# Xbee_Remote_v1_0.net
KiCad netlist of a schematic drawn in EAGLE
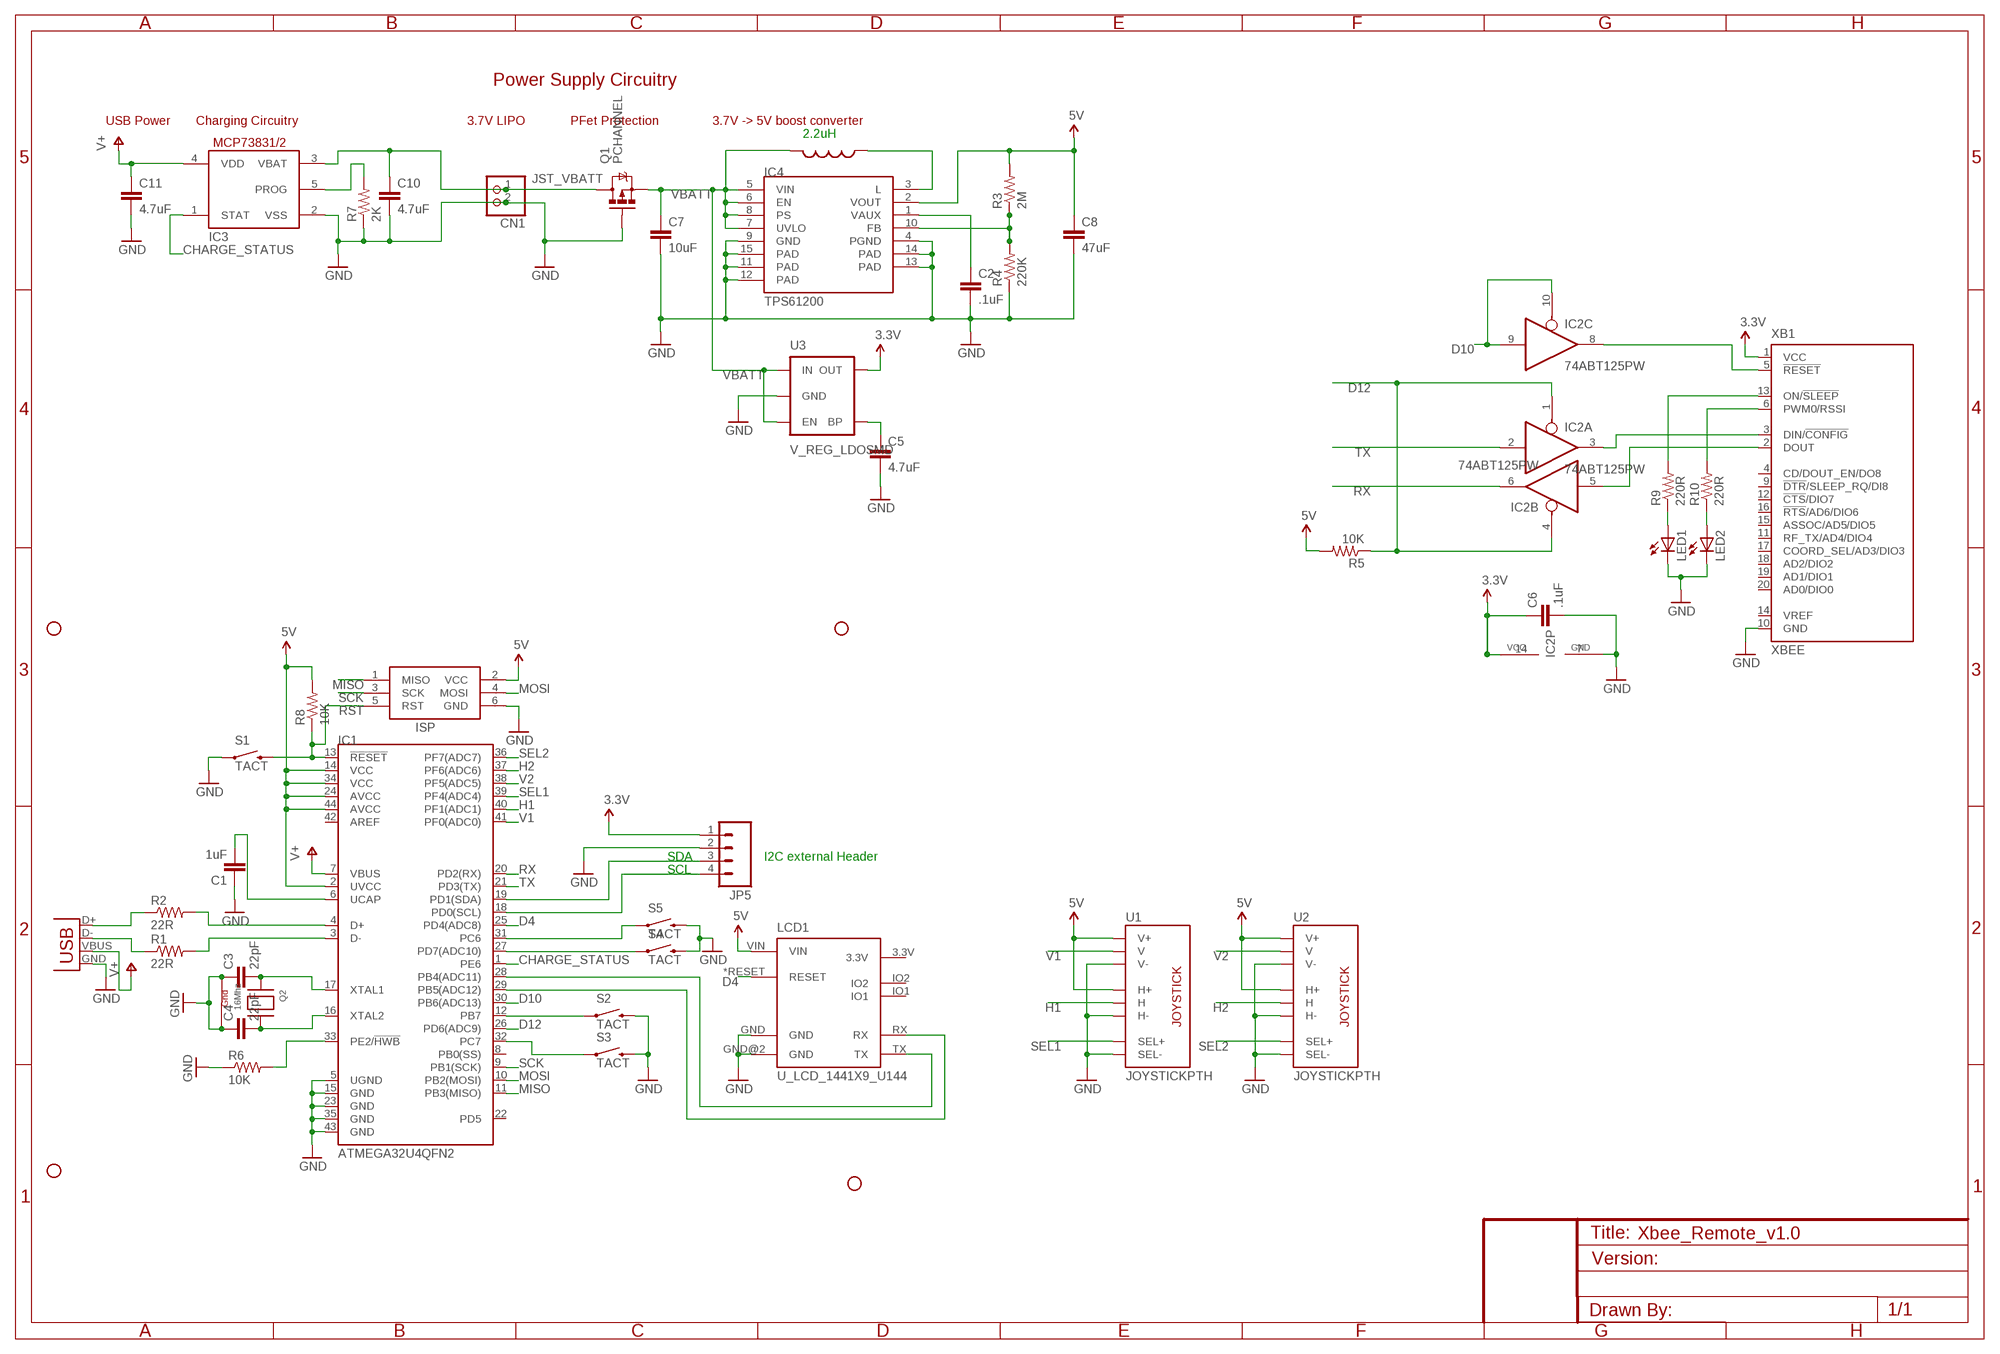
[diagram p0: schematic, sheet 1]

(export (version "E")
  (design (tool "Eeschema 10.0.6"))
  (components
    (comp (ref "C1")
      (value "1uF")
      (footprint "eagle-import:0805")
      (libsource (lib "eagle-import") (part "CAP0805"))
    )
    (comp (ref "C2")
      (value ".1uF")
      (footprint "eagle-import:0805")
      (libsource (lib "eagle-import") (part "CAP0805"))
    )
    (comp (ref "C3")
      (value "22pF")
      (footprint "eagle-import:0805")
      (libsource (lib "eagle-import") (part "CAP0805"))
    )
    (comp (ref "C4")
      (value "22pF")
      (footprint "eagle-import:0805")
      (libsource (lib "eagle-import") (part "CAP0805"))
    )
    (comp (ref "C5")
      (value "4.7uF")
      (footprint "eagle-import:0805")
      (libsource (lib "eagle-import") (part "CAP0805"))
    )
    (comp (ref "C6")
      (value ".1uF")
      (footprint "eagle-import:0805")
      (libsource (lib "eagle-import") (part "CAP0805"))
    )
    (comp (ref "C7")
      (value "10uF")
      (footprint "eagle-import:0805")
      (libsource (lib "eagle-import") (part "CAP0805"))
    )
    (comp (ref "C8")
      (value "47uF")
      (footprint "eagle-import:1206")
      (libsource (lib "eagle-import") (part "CAP1206"))
    )
    (comp (ref "C10")
      (value "4.7uF")
      (footprint "eagle-import:0805")
      (libsource (lib "eagle-import") (part "CAP0805"))
    )
    (comp (ref "C11")
      (value "4.7uF")
      (footprint "eagle-import:0805")
      (libsource (lib "eagle-import") (part "CAP0805"))
    )
    (comp (ref "CN1")
      (value "JST_2PIN-SMT-RA")
      (footprint "eagle-import:JST-PH-2-SMT-RA")
      (libsource (lib "eagle-import") (part "JST_2PIN-SMT-RA"))
    )
    (comp (ref "IC1")
      (value "ATMEGA32U4QFN2")
      (footprint "eagle-import:QFN-44-NOPAD")
      (libsource (lib "eagle-import") (part "ATMEGA32U4QFN2"))
    )
    (comp (ref "IC2")
      (value "74ABT125PW")
      (footprint "eagle-import:TSSOP14")
      (libsource (lib "eagle-import") (part "74125PWABT"))
    )
    (comp (ref "IC3")
      (value "MCP73831/OT")
      (footprint "eagle-import:SOT23-5L")
      (libsource (lib "eagle-import") (part "MCP73831/OT"))
    )
    (comp (ref "IC4")
      (value "TPS61200")
      (footprint "eagle-import:QFN-10_PAD")
      (libsource (lib "eagle-import") (part "TPS61200"))
    )
    (comp (ref "ISP")
      (value "AVRISP-6")
      (footprint "eagle-import:AVRISP")
      (libsource (lib "eagle-import") (part "AVRISP-6"))
    )
    (comp (ref "JP1")
      (value "STAND-OFF")
      (footprint "eagle-import:STAND-OFF")
      (libsource (lib "eagle-import") (part "STAND-OFF"))
    )
    (comp (ref "JP2")
      (value "STAND-OFF")
      (footprint "eagle-import:STAND-OFF")
      (libsource (lib "eagle-import") (part "STAND-OFF"))
    )
    (comp (ref "JP3")
      (value "STAND-OFF")
      (footprint "eagle-import:STAND-OFF")
      (libsource (lib "eagle-import") (part "STAND-OFF"))
    )
    (comp (ref "JP4")
      (value "STAND-OFF")
      (footprint "eagle-import:STAND-OFF")
      (libsource (lib "eagle-import") (part "STAND-OFF"))
    )
    (comp (ref "JP5")
      (value "M04PTH")
      (footprint "eagle-import:1X04")
      (libsource (lib "eagle-import") (part "M04PTH"))
    )
    (comp (ref "L1")
      (value "2.2uH")
      (footprint "eagle-import:COILCRAFT_EPL2014")
      (libsource (lib "eagle-import") (part "INDUCTOREPL2014"))
    )
    (comp (ref "LCD1")
      (value "U_LCD_1441X9_U144")
      (footprint "eagle-import:U_LCD_144")
      (libsource (lib "eagle-import") (part "U_LCD_1441X9_U144"))
    )
    (comp (ref "LED1")
      (value "LEDCHIPLED_0805")
      (footprint "eagle-import:CHIPLED_0805")
      (libsource (lib "eagle-import") (part "LEDCHIPLED_0805"))
    )
    (comp (ref "LED2")
      (value "LEDCHIPLED_0805")
      (footprint "eagle-import:CHIPLED_0805")
      (libsource (lib "eagle-import") (part "LEDCHIPLED_0805"))
    )
    (comp (ref "Q1")
      (value "PCHANNEL")
      (footprint "eagle-import:SOT23-3")
      (libsource (lib "eagle-import") (part "MOSFET-PCHANNELSMD"))
    )
    (comp (ref "Q2")
      (value "16Mhz")
      (footprint "eagle-import:NX3225")
      (libsource (lib "eagle-import") (part "XTAL-4-3225"))
    )
    (comp (ref "R1")
      (value "22R")
      (footprint "eagle-import:0805")
      (libsource (lib "eagle-import") (part "RESISTOR"))
    )
    (comp (ref "R2")
      (value "22R")
      (footprint "eagle-import:0805")
      (libsource (lib "eagle-import") (part "RESISTOR"))
    )
    (comp (ref "R3")
      (value "2M")
      (footprint "eagle-import:0805")
      (libsource (lib "eagle-import") (part "RESISTOR"))
    )
    (comp (ref "R4")
      (value "220K")
      (footprint "eagle-import:0805")
      (libsource (lib "eagle-import") (part "RESISTOR"))
    )
    (comp (ref "R5")
      (value "10K")
      (footprint "eagle-import:0805")
      (libsource (lib "eagle-import") (part "RESISTOR"))
    )
    (comp (ref "R6")
      (value "10K")
      (footprint "eagle-import:0805")
      (libsource (lib "eagle-import") (part "RESISTOR"))
    )
    (comp (ref "R7")
      (value "2K")
      (footprint "eagle-import:0805")
      (libsource (lib "eagle-import") (part "RESISTOR"))
    )
    (comp (ref "R8")
      (value "10K")
      (footprint "eagle-import:0805")
      (libsource (lib "eagle-import") (part "RESISTOR"))
    )
    (comp (ref "R9")
      (value "220R")
      (footprint "eagle-import:0805")
      (libsource (lib "eagle-import") (part "RESISTOR"))
    )
    (comp (ref "R10")
      (value "220R")
      (footprint "eagle-import:0805")
      (libsource (lib "eagle-import") (part "RESISTOR"))
    )
    (comp (ref "S1")
      (value "TACT")
      (footprint "eagle-import:TACTILE_SWITCH_SMD")
      (libsource (lib "eagle-import") (part "SWITCH-MOMENTARY-2SMD"))
    )
    (comp (ref "S2")
      (value "TACT")
      (footprint "eagle-import:TACTILE_SWITCH_SMD")
      (libsource (lib "eagle-import") (part "SWITCH-MOMENTARY-2SMD"))
    )
    (comp (ref "S3")
      (value "TACT")
      (footprint "eagle-import:TACTILE_SWITCH_SMD")
      (libsource (lib "eagle-import") (part "SWITCH-MOMENTARY-2SMD"))
    )
    (comp (ref "S4")
      (value "TACT")
      (footprint "eagle-import:TACTILE_SWITCH_SMD")
      (libsource (lib "eagle-import") (part "SWITCH-MOMENTARY-2SMD"))
    )
    (comp (ref "S5")
      (value "TACT")
      (footprint "eagle-import:TACTILE_SWITCH_SMD")
      (libsource (lib "eagle-import") (part "SWITCH-MOMENTARY-2SMD"))
    )
    (comp (ref "U1")
      (value "JOYSTICKPTH")
      (footprint "eagle-import:JOYSTICK")
      (libsource (lib "eagle-import") (part "JOYSTICKPTH"))
    )
    (comp (ref "U2")
      (value "JOYSTICKPTH")
      (footprint "eagle-import:JOYSTICK")
      (libsource (lib "eagle-import") (part "JOYSTICKPTH"))
    )
    (comp (ref "U3")
      (value "V_REG_LDOSMD")
      (footprint "eagle-import:SOT23-5")
      (libsource (lib "eagle-import") (part "V_REG_LDOSMD"))
    )
    (comp (ref "X1")
      (value "USB-MICROB")
      (footprint "eagle-import:USB-MICROB")
      (libsource (lib "eagle-import") (part "USB-MICROB"))
    )
    (comp (ref "XB1")
      (value "XBEE")
      (footprint "eagle-import:XBEE")
      (fields (field (name "MPN") "XBP24-Z7UIT-004"))
      (libsource (lib "eagle-import") (part "XBEE"))
    )
  )
  (nets
    (net (code "1") (name "/CHARGE_STATUS") (class "Default")
      (node (ref "IC1") (pin "1") (pinfunction "PE6_1") (pintype "bidirectional"))
      (node (ref "IC3") (pin "1") (pinfunction "STAT_1") (pintype "output"))
    )
    (net (code "2") (name "/D4") (class "Default")
      (node (ref "IC1") (pin "25") (pinfunction "PD4(ADC8)_25") (pintype "bidirectional"))
      (node (ref "LCD1") (pin "*RESET") (pinfunction "RESET_*RESET") (pintype "input"))
    )
    (net (code "3") (name "/D10") (class "Default")
      (node (ref "IC1") (pin "30") (pinfunction "PB6(ADC13)_30") (pintype "bidirectional"))
      (node (ref "IC2") (pin "10") (pinfunction "OE_10") (pintype "input"))
      (node (ref "IC2") (pin "9") (pinfunction "I_9") (pintype "input"))
    )
    (net (code "4") (name "/D12") (class "Default")
      (node (ref "IC1") (pin "26") (pinfunction "PD6(ADC9)_26") (pintype "bidirectional"))
      (node (ref "IC2") (pin "1") (pinfunction "OE_1") (pintype "input"))
      (node (ref "IC2") (pin "4") (pinfunction "OE_4") (pintype "input"))
      (node (ref "R5") (pin "1") (pinfunction "1_1") (pintype "passive"))
    )
    (net (code "5") (name "/H1") (class "Default")
      (node (ref "IC1") (pin "40") (pinfunction "PF1(ADC1)_40") (pintype "bidirectional"))
      (node (ref "U1") (pin "H2") (pinfunction "H_H2") (pintype "bidirectional"))
    )
    (net (code "6") (name "/H2") (class "Default")
      (node (ref "IC1") (pin "37") (pinfunction "PF6(ADC6)_37") (pintype "bidirectional"))
      (node (ref "U2") (pin "H2") (pinfunction "H_H2") (pintype "bidirectional"))
    )
    (net (code "7") (name "/JST_VBATT") (class "Default")
      (node (ref "C10") (pin "1") (pinfunction "1_1") (pintype "passive"))
      (node (ref "CN1") (pin "1") (pinfunction "2_1") (pintype "passive"))
      (node (ref "IC3") (pin "3") (pinfunction "VBAT_3") (pintype "bidirectional"))
      (node (ref "Q1") (pin "3") (pinfunction "D_3") (pintype "passive"))
    )
    (net (code "8") (name "/MISO") (class "Default")
      (node (ref "IC1") (pin "11") (pinfunction "PB3(MISO)_11") (pintype "bidirectional"))
      (node (ref "ISP") (pin "1") (pinfunction "MISO_1") (pintype "input"))
    )
    (net (code "9") (name "/MOSI") (class "Default")
      (node (ref "IC1") (pin "10") (pinfunction "PB2(MOSI)_10") (pintype "bidirectional"))
      (node (ref "ISP") (pin "4") (pinfunction "MOSI_4") (pintype "output"))
    )
    (net (code "10") (name "/RST") (class "Default")
      (node (ref "IC1") (pin "13") (pinfunction "~{RESET}_13") (pintype "bidirectional"))
      (node (ref "ISP") (pin "5") (pinfunction "RST_5") (pintype "output"))
      (node (ref "R8") (pin "1") (pinfunction "1_1") (pintype "passive"))
      (node (ref "S1") (pin "3") (pinfunction "2_3") (pintype "passive"))
    )
    (net (code "11") (name "/RX") (class "Default")
      (node (ref "IC1") (pin "20") (pinfunction "PD2(RX)_20") (pintype "bidirectional"))
      (node (ref "IC2") (pin "6") (pinfunction "O_6") (pintype "tri_state"))
    )
    (net (code "12") (name "/SCK") (class "Default")
      (node (ref "IC1") (pin "9") (pinfunction "PB1(SCK)_9") (pintype "bidirectional"))
      (node (ref "ISP") (pin "3") (pinfunction "SCK_3") (pintype "output"))
    )
    (net (code "13") (name "/SEL1") (class "Default")
      (node (ref "IC1") (pin "39") (pinfunction "PF4(ADC4)_39") (pintype "bidirectional"))
      (node (ref "U1") (pin "B1A") (pinfunction "SEL+_B1A") (pintype "bidirectional"))
    )
    (net (code "14") (name "/SEL2") (class "Default")
      (node (ref "IC1") (pin "36") (pinfunction "PF7(ADC7)_36") (pintype "bidirectional"))
      (node (ref "U2") (pin "B1A") (pinfunction "SEL+_B1A") (pintype "bidirectional"))
    )
    (net (code "15") (name "/TX") (class "Default")
      (node (ref "IC1") (pin "21") (pinfunction "PD3(TX)_21") (pintype "bidirectional"))
      (node (ref "IC2") (pin "2") (pinfunction "I_2") (pintype "input"))
    )
    (net (code "16") (name "/V1") (class "Default")
      (node (ref "IC1") (pin "41") (pinfunction "PF0(ADC0)_41") (pintype "bidirectional"))
      (node (ref "U1") (pin "V2") (pinfunction "V_V2") (pintype "bidirectional"))
    )
    (net (code "17") (name "/V2") (class "Default")
      (node (ref "IC1") (pin "38") (pinfunction "PF5(ADC5)_38") (pintype "bidirectional"))
      (node (ref "U2") (pin "V2") (pinfunction "V_V2") (pintype "bidirectional"))
    )
    (net (code "18") (name "/VBATT") (class "Default")
      (node (ref "C7") (pin "1") (pinfunction "1_1") (pintype "passive"))
      (node (ref "IC4") (pin "5") (pinfunction "VIN_5") (pintype "power_in"))
      (node (ref "IC4") (pin "6") (pinfunction "EN_6") (pintype "input"))
      (node (ref "IC4") (pin "7") (pinfunction "UVLO_7") (pintype "passive"))
      (node (ref "IC4") (pin "8") (pinfunction "PS_8") (pintype "input"))
      (node (ref "L1") (pin "P$2") (pinfunction "2_P$2") (pintype "bidirectional"))
      (node (ref "Q1") (pin "2") (pinfunction "S_2") (pintype "passive"))
      (node (ref "U3") (pin "1") (pinfunction "IN_1") (pintype "input"))
      (node (ref "U3") (pin "3") (pinfunction "EN_3") (pintype "input"))
    )
    (net (code "19") (name "3.3V") (class "Default")
      (node (ref "C6") (pin "1") (pinfunction "1_1") (pintype "passive"))
      (node (ref "IC2") (pin "14") (pinfunction "VCC_14") (pintype "power_in"))
      (node (ref "JP5") (pin "1") (pinfunction "1_1") (pintype "passive"))
      (node (ref "U3") (pin "5") (pinfunction "OUT_5") (pintype "passive"))
      (node (ref "XB1") (pin "1") (pinfunction "VCC_1") (pintype "power_in"))
    )
    (net (code "20") (name "5V") (class "Default")
      (node (ref "C8") (pin "1") (pinfunction "1_1") (pintype "passive"))
      (node (ref "IC1") (pin "14") (pinfunction "VCC_14") (pintype "bidirectional"))
      (node (ref "IC1") (pin "2") (pinfunction "UVCC_2") (pintype "bidirectional"))
      (node (ref "IC1") (pin "24") (pinfunction "AVCC_24") (pintype "bidirectional"))
      (node (ref "IC1") (pin "34") (pinfunction "VCC_34") (pintype "bidirectional"))
      (node (ref "IC1") (pin "44") (pinfunction "AVCC_44") (pintype "bidirectional"))
      (node (ref "IC4") (pin "2") (pinfunction "VOUT_2") (pintype "passive"))
      (node (ref "ISP") (pin "2") (pinfunction "VCC_2") (pintype "power_in"))
      (node (ref "LCD1") (pin "VIN") (pinfunction "VIN_VIN") (pintype "power_in"))
      (node (ref "R3") (pin "2") (pinfunction "2_2") (pintype "passive"))
      (node (ref "R5") (pin "2") (pinfunction "2_2") (pintype "passive"))
      (node (ref "R8") (pin "2") (pinfunction "2_2") (pintype "passive"))
      (node (ref "U1") (pin "H1") (pinfunction "H+_H1") (pintype "bidirectional"))
      (node (ref "U1") (pin "V1") (pinfunction "V+_V1") (pintype "bidirectional"))
      (node (ref "U2") (pin "H1") (pinfunction "H+_H1") (pintype "bidirectional"))
      (node (ref "U2") (pin "V1") (pinfunction "V+_V1") (pintype "bidirectional"))
    )
    (net (code "21") (name "GND") (class "Default")
      (node (ref "C1") (pin "1") (pinfunction "1_1") (pintype "passive"))
      (node (ref "C10") (pin "2") (pinfunction "2_2") (pintype "passive"))
      (node (ref "C11") (pin "2") (pinfunction "2_2") (pintype "passive"))
      (node (ref "C2") (pin "2") (pinfunction "2_2") (pintype "passive"))
      (node (ref "C3") (pin "1") (pinfunction "1_1") (pintype "passive"))
      (node (ref "C4") (pin "1") (pinfunction "1_1") (pintype "passive"))
      (node (ref "C5") (pin "2") (pinfunction "2_2") (pintype "passive"))
      (node (ref "C6") (pin "2") (pinfunction "2_2") (pintype "passive"))
      (node (ref "C7") (pin "2") (pinfunction "2_2") (pintype "passive"))
      (node (ref "C8") (pin "2") (pinfunction "2_2") (pintype "passive"))
      (node (ref "CN1") (pin "2") (pinfunction "1_2") (pintype "passive"))
      (node (ref "IC1") (pin "15") (pinfunction "GND_15") (pintype "bidirectional"))
      (node (ref "IC1") (pin "23") (pinfunction "GND_23") (pintype "bidirectional"))
      (node (ref "IC1") (pin "35") (pinfunction "GND_35") (pintype "bidirectional"))
      (node (ref "IC1") (pin "43") (pinfunction "GND_43") (pintype "bidirectional"))
      (node (ref "IC1") (pin "5") (pinfunction "UGND_5") (pintype "bidirectional"))
      (node (ref "IC2") (pin "7") (pinfunction "GND_7") (pintype "power_in"))
      (node (ref "IC3") (pin "2") (pinfunction "VSS_2") (pintype "power_in"))
      (node (ref "IC4") (pin "11") (pinfunction "PAD_11") (pintype "power_in"))
      (node (ref "IC4") (pin "12") (pinfunction "PAD_12") (pintype "power_in"))
      (node (ref "IC4") (pin "13") (pinfunction "PAD_13") (pintype "power_in"))
      (node (ref "IC4") (pin "14") (pinfunction "PAD_14") (pintype "power_in"))
      (node (ref "IC4") (pin "15") (pinfunction "PAD_15") (pintype "power_in"))
      (node (ref "IC4") (pin "4") (pinfunction "PGND_4") (pintype "power_in"))
      (node (ref "IC4") (pin "9") (pinfunction "GND_9") (pintype "power_in"))
      (node (ref "ISP") (pin "6") (pinfunction "GND_6") (pintype "power_in"))
      (node (ref "JP5") (pin "2") (pinfunction "2_2") (pintype "passive"))
      (node (ref "LCD1") (pin "GND") (pinfunction "GND_GND") (pintype "power_in"))
      (node (ref "LCD1") (pin "GND@2") (pinfunction "GND_GND@2") (pintype "power_in"))
      (node (ref "LED1") (pin "C") (pinfunction "C_C") (pintype "passive"))
      (node (ref "LED2") (pin "C") (pinfunction "C_C") (pintype "passive"))
      (node (ref "Q1") (pin "1") (pinfunction "G_1") (pintype "passive"))
      (node (ref "Q2") (pin "2") (pinfunction "G1_2") (pintype "power_in"))
      (node (ref "Q2") (pin "4") (pinfunction "G2_4") (pintype "power_in"))
      (node (ref "R4") (pin "1") (pinfunction "1_1") (pintype "passive"))
      (node (ref "R6") (pin "1") (pinfunction "1_1") (pintype "passive"))
      (node (ref "R7") (pin "1") (pinfunction "1_1") (pintype "passive"))
      (node (ref "S1") (pin "1") (pinfunction "1_1") (pintype "passive"))
      (node (ref "S2") (pin "3") (pinfunction "2_3") (pintype "passive"))
      (node (ref "S3") (pin "3") (pinfunction "2_3") (pintype "passive"))
      (node (ref "S4") (pin "3") (pinfunction "2_3") (pintype "passive"))
      (node (ref "S5") (pin "3") (pinfunction "2_3") (pintype "passive"))
      (node (ref "U1") (pin "B2A") (pinfunction "SEL-_B2A") (pintype "bidirectional"))
      (node (ref "U1") (pin "H3") (pinfunction "H-_H3") (pintype "bidirectional"))
      (node (ref "U1") (pin "V3") (pinfunction "V-_V3") (pintype "bidirectional"))
      (node (ref "U2") (pin "B2A") (pinfunction "SEL-_B2A") (pintype "bidirectional"))
      (node (ref "U2") (pin "H3") (pinfunction "H-_H3") (pintype "bidirectional"))
      (node (ref "U2") (pin "V3") (pinfunction "V-_V3") (pintype "bidirectional"))
      (node (ref "U3") (pin "2") (pinfunction "GND_2") (pintype "input"))
      (node (ref "X1") (pin "GND") (pinfunction "GND_GND") (pintype "bidirectional"))
      (node (ref "XB1") (pin "10") (pinfunction "GND_10") (pintype "power_in"))
    )
    (net (code "22") (name "Net-(IC1-D+)") (class "Default")
      (node (ref "IC1") (pin "4") (pinfunction "D+_4") (pintype "bidirectional"))
      (node (ref "R2") (pin "2") (pinfunction "2_2") (pintype "passive"))
    )
    (net (code "23") (name "Net-(IC1-D-)") (class "Default")
      (node (ref "IC1") (pin "3") (pinfunction "D-_3") (pintype "bidirectional"))
      (node (ref "R1") (pin "2") (pinfunction "2_2") (pintype "passive"))
    )
    (net (code "24") (name "Net-(IC1-PB4(ADC11))") (class "Default")
      (node (ref "IC1") (pin "28") (pinfunction "PB4(ADC11)_28") (pintype "bidirectional"))
      (node (ref "LCD1") (pin "TX") (pinfunction "TX_TX") (pintype "output"))
    )
    (net (code "25") (name "Net-(IC1-PB5(ADC12))") (class "Default")
      (node (ref "IC1") (pin "29") (pinfunction "PB5(ADC12)_29") (pintype "bidirectional"))
      (node (ref "LCD1") (pin "RX") (pinfunction "RX_RX") (pintype "input"))
    )
    (net (code "26") (name "Net-(IC1-PB7)") (class "Default")
      (node (ref "IC1") (pin "12") (pinfunction "PB7_12") (pintype "bidirectional"))
      (node (ref "S2") (pin "1") (pinfunction "1_1") (pintype "passive"))
    )
    (net (code "27") (name "Net-(IC1-PC6)") (class "Default")
      (node (ref "IC1") (pin "31") (pinfunction "PC6_31") (pintype "bidirectional"))
      (node (ref "S5") (pin "1") (pinfunction "1_1") (pintype "passive"))
    )
    (net (code "28") (name "Net-(IC1-PC7)") (class "Default")
      (node (ref "IC1") (pin "32") (pinfunction "PC7_32") (pintype "bidirectional"))
      (node (ref "S3") (pin "1") (pinfunction "1_1") (pintype "passive"))
    )
    (net (code "29") (name "Net-(IC1-PD0(SCL))") (class "Default")
      (node (ref "IC1") (pin "18") (pinfunction "PD0(SCL)_18") (pintype "bidirectional"))
      (node (ref "JP5") (pin "4") (pinfunction "4_4") (pintype "passive"))
    )
    (net (code "30") (name "Net-(IC1-PD1(SDA))") (class "Default")
      (node (ref "IC1") (pin "19") (pinfunction "PD1(SDA)_19") (pintype "bidirectional"))
      (node (ref "JP5") (pin "3") (pinfunction "3_3") (pintype "passive"))
    )
    (net (code "31") (name "Net-(IC1-PD7(ADC10))") (class "Default")
      (node (ref "IC1") (pin "27") (pinfunction "PD7(ADC10)_27") (pintype "bidirectional"))
      (node (ref "S4") (pin "1") (pinfunction "1_1") (pintype "passive"))
    )
    (net (code "32") (name "Net-(IC1-PE2{slash}~{HWB})") (class "Default")
      (node (ref "IC1") (pin "33") (pinfunction "PE2/~{HWB}_33") (pintype "bidirectional"))
      (node (ref "R6") (pin "2") (pinfunction "2_2") (pintype "passive"))
    )
    (net (code "33") (name "Net-(IC1-UCAP)") (class "Default")
      (node (ref "C1") (pin "2") (pinfunction "2_2") (pintype "passive"))
      (node (ref "IC1") (pin "6") (pinfunction "UCAP_6") (pintype "bidirectional"))
    )
    (net (code "34") (name "Net-(IC1-XTAL1)") (class "Default")
      (node (ref "C3") (pin "2") (pinfunction "2_2") (pintype "passive"))
      (node (ref "IC1") (pin "17") (pinfunction "XTAL1_17") (pintype "bidirectional"))
      (node (ref "Q2") (pin "1") (pinfunction "X1_1") (pintype "bidirectional"))
    )
    (net (code "35") (name "Net-(IC1-XTAL2)") (class "Default")
      (node (ref "C4") (pin "2") (pinfunction "2_2") (pintype "passive"))
      (node (ref "IC1") (pin "16") (pinfunction "XTAL2_16") (pintype "bidirectional"))
      (node (ref "Q2") (pin "3") (pinfunction "X2_3") (pintype "bidirectional"))
    )
    (net (code "36") (name "Net-(IC2A-O)") (class "Default")
      (node (ref "IC2") (pin "3") (pinfunction "O_3") (pintype "tri_state"))
      (node (ref "XB1") (pin "3") (pinfunction "DIN/~{CONFIG}_3") (pintype "input"))
    )
    (net (code "37") (name "Net-(IC2B-I)") (class "Default")
      (node (ref "IC2") (pin "5") (pinfunction "I_5") (pintype "input"))
      (node (ref "XB1") (pin "2") (pinfunction "DOUT_2") (pintype "output"))
    )
    (net (code "38") (name "Net-(IC2C-O)") (class "Default")
      (node (ref "IC2") (pin "8") (pinfunction "O_8") (pintype "tri_state"))
      (node (ref "XB1") (pin "5") (pinfunction "~{RESET}_5") (pintype "input"))
    )
    (net (code "39") (name "Net-(IC3-PROG)") (class "Default")
      (node (ref "IC3") (pin "5") (pinfunction "PROG_5") (pintype "input"))
      (node (ref "R7") (pin "2") (pinfunction "2_2") (pintype "passive"))
    )
    (net (code "40") (name "Net-(IC4-FB)") (class "Default")
      (node (ref "IC4") (pin "10") (pinfunction "FB_10") (pintype "passive"))
      (node (ref "R3") (pin "1") (pinfunction "1_1") (pintype "passive"))
      (node (ref "R4") (pin "2") (pinfunction "2_2") (pintype "passive"))
    )
    (net (code "41") (name "Net-(IC4-L)") (class "Default")
      (node (ref "IC4") (pin "3") (pinfunction "L_3") (pintype "passive"))
      (node (ref "L1") (pin "P$1") (pinfunction "1_P$1") (pintype "bidirectional"))
    )
    (net (code "42") (name "Net-(IC4-VAUX)") (class "Default")
      (node (ref "C2") (pin "1") (pinfunction "1_1") (pintype "passive"))
      (node (ref "IC4") (pin "1") (pinfunction "VAUX_1") (pintype "passive"))
    )
    (net (code "43") (name "Net-(LED1-PadA)") (class "Default")
      (node (ref "LED1") (pin "A") (pinfunction "A_A") (pintype "passive"))
      (node (ref "R9") (pin "1") (pinfunction "1_1") (pintype "passive"))
    )
    (net (code "44") (name "Net-(LED2-PadA)") (class "Default")
      (node (ref "LED2") (pin "A") (pinfunction "A_A") (pintype "passive"))
      (node (ref "R10") (pin "1") (pinfunction "1_1") (pintype "passive"))
    )
    (net (code "45") (name "Net-(R1-Pad1)") (class "Default")
      (node (ref "R1") (pin "1") (pinfunction "1_1") (pintype "passive"))
      (node (ref "X1") (pin "D-") (pinfunction "D-_D-") (pintype "bidirectional"))
    )
    (net (code "46") (name "Net-(R2-Pad1)") (class "Default")
      (node (ref "R2") (pin "1") (pinfunction "1_1") (pintype "passive"))
      (node (ref "X1") (pin "D+") (pinfunction "D+_D+") (pintype "bidirectional"))
    )
    (net (code "47") (name "Net-(U3-BP)") (class "Default")
      (node (ref "C5") (pin "1") (pinfunction "1_1") (pintype "passive"))
      (node (ref "U3") (pin "4") (pinfunction "BP_4") (pintype "input"))
    )
    (net (code "48") (name "Net-(XB1-ON{slash}~{SLEEP})") (class "Default")
      (node (ref "R9") (pin "2") (pinfunction "2_2") (pintype "passive"))
      (node (ref "XB1") (pin "13") (pinfunction "ON/~{SLEEP}_13") (pintype "output"))
    )
    (net (code "49") (name "Net-(XB1-PWM0{slash}RSSI)") (class "Default")
      (node (ref "R10") (pin "2") (pinfunction "2_2") (pintype "passive"))
      (node (ref "XB1") (pin "6") (pinfunction "PWM0/RSSI_6") (pintype "output"))
    )
    (net (code "50") (name "V+") (class "Default")
      (node (ref "C11") (pin "1") (pinfunction "1_1") (pintype "passive"))
      (node (ref "IC1") (pin "7") (pinfunction "VBUS_7") (pintype "bidirectional"))
      (node (ref "IC3") (pin "4") (pinfunction "VDD_4") (pintype "power_in"))
      (node (ref "X1") (pin "VBUS") (pinfunction "VBUS_VBUS") (pintype "bidirectional"))
    )
    (net (code "51") (name "unconnected-(IC1-AREF-Pad42)") (class "Default")
      (node (ref "IC1") (pin "42") (pinfunction "AREF_42") (pintype "bidirectional"))
    )
    (net (code "52") (name "unconnected-(IC1-PB0(SS)-Pad8)") (class "Default")
      (node (ref "IC1") (pin "8") (pinfunction "PB0(SS)_8") (pintype "bidirectional"))
    )
    (net (code "53") (name "unconnected-(IC1-PD5-Pad22)") (class "Default")
      (node (ref "IC1") (pin "22") (pinfunction "PD5_22") (pintype "bidirectional"))
    )
    (net (code "54") (name "unconnected-(LCD1-Pad3.3V)") (class "Default")
      (node (ref "LCD1") (pin "3.3V") (pinfunction "3.3V_3.3V") (pintype "output"))
    )
    (net (code "55") (name "unconnected-(LCD1-PadIO1)") (class "Default")
      (node (ref "LCD1") (pin "IO1") (pinfunction "IO1_IO1") (pintype "bidirectional"))
    )
    (net (code "56") (name "unconnected-(LCD1-PadIO2)") (class "Default")
      (node (ref "LCD1") (pin "IO2") (pinfunction "IO2_IO2") (pintype "bidirectional"))
    )
    (net (code "57") (name "unconnected-(XB1-AD0{slash}DIO0-Pad20)") (class "Default")
      (node (ref "XB1") (pin "20") (pinfunction "AD0/DIO0_20") (pintype "bidirectional"))
    )
    (net (code "58") (name "unconnected-(XB1-AD1{slash}DIO1-Pad19)") (class "Default")
      (node (ref "XB1") (pin "19") (pinfunction "AD1/DIO1_19") (pintype "bidirectional"))
    )
    (net (code "59") (name "unconnected-(XB1-AD2{slash}DIO2-Pad18)") (class "Default")
      (node (ref "XB1") (pin "18") (pinfunction "AD2/DIO2_18") (pintype "bidirectional"))
    )
    (net (code "60") (name "unconnected-(XB1-ASSOC{slash}AD5{slash}DIO5-Pad15)") (class "Default")
      (node (ref "XB1") (pin "15") (pinfunction "ASSOC/AD5/DIO5_15") (pintype "bidirectional"))
    )
    (net (code "61") (name "unconnected-(XB1-CD{slash}DOUT_EN{slash}DO8-Pad4)") (class "Default")
      (node (ref "XB1") (pin "4") (pinfunction "CD/DOUT_EN/DO8_4") (pintype "output"))
    )
    (net (code "62") (name "unconnected-(XB1-COORD_SEL{slash}AD3{slash}DIO3-Pad17)") (class "Default")
      (node (ref "XB1") (pin "17") (pinfunction "COORD_SEL/AD3/DIO3_17") (pintype "bidirectional"))
    )
    (net (code "63") (name "unconnected-(XB1-RF_TX{slash}AD4{slash}DIO4-Pad11)") (class "Default")
      (node (ref "XB1") (pin "11") (pinfunction "RF_TX/AD4/DIO4_11") (pintype "bidirectional"))
    )
    (net (code "64") (name "unconnected-(XB1-VREF-Pad14)") (class "Default")
      (node (ref "XB1") (pin "14") (pinfunction "VREF_14") (pintype "input"))
    )
    (net (code "65") (name "unconnected-(XB1-~{CTS}{slash}DIO7-Pad12)") (class "Default")
      (node (ref "XB1") (pin "12") (pinfunction "~{CTS}/DIO7_12") (pintype "bidirectional"))
    )
    (net (code "66") (name "unconnected-(XB1-~{DTR}{slash}SLEEP_RQ{slash}DI8-Pad9)") (class "Default")
      (node (ref "XB1") (pin "9") (pinfunction "~{DTR}/SLEEP_RQ/DI8_9") (pintype "bidirectional"))
    )
    (net (code "67") (name "unconnected-(XB1-~{RTS}{slash}AD6{slash}DIO6-Pad16)") (class "Default")
      (node (ref "XB1") (pin "16") (pinfunction "~{RTS}/AD6/DIO6_16") (pintype "bidirectional"))
    )
  )
)
